# SimpleCharger-LiIon-OpampBased-LM358.net
KiCad netlist of a schematic drawn in EAGLE
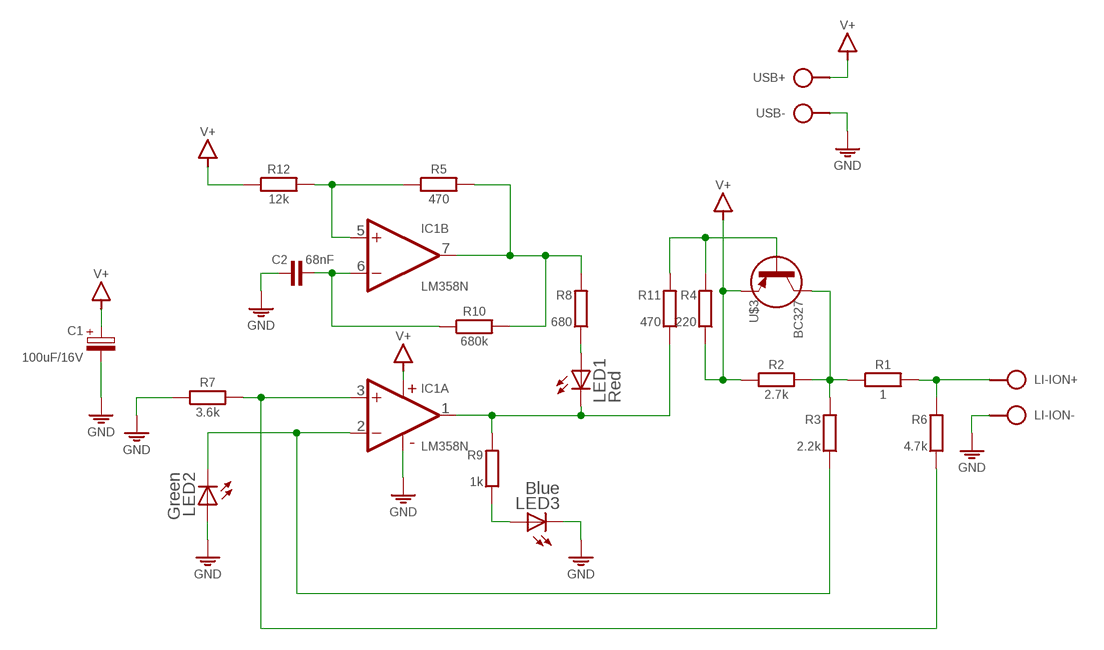
[diagram p0: schematic, sheet 1]

(export (version "E")
  (design (tool "Eeschema 10.0.6"))
  (components
    (comp (ref "C1")
      (value "100uF/16V")
      (footprint "eagle-import:E2,5-5")
      (libsource (lib "eagle-import") (part "CPOLE2.5-5"))
    )
    (comp (ref "C2")
      (value "68nF")
      (footprint "eagle-import:C075-020X044_V")
      (libsource (lib "eagle-import") (part "C-H075-020X044/V"))
    )
    (comp (ref "IC1")
      (value "LM358N")
      (footprint "eagle-import:DIL08")
      (libsource (lib "eagle-import") (part "LM358N"))
    )
    (comp (ref "LED1")
      (value "Red")
      (footprint "eagle-import:LED3MM")
      (libsource (lib "eagle-import") (part "LED3MM"))
    )
    (comp (ref "LED2")
      (value "Green")
      (footprint "eagle-import:LED3MM")
      (libsource (lib "eagle-import") (part "LED3MM"))
    )
    (comp (ref "LED3")
      (value "Blue")
      (footprint "eagle-import:LED3MM")
      (libsource (lib "eagle-import") (part "LED3MM"))
    )
    (comp (ref "LI-ION")
      (value "SPAD+-+-")
      (footprint "eagle-import:SPAD+-")
      (libsource (lib "eagle-import") (part "SPAD+-+-"))
    )
    (comp (ref "R1")
      (value "1")
      (footprint "eagle-import:0204_10")
      (libsource (lib "eagle-import") (part "R-H0204/10"))
    )
    (comp (ref "R2")
      (value "2.7k")
      (footprint "eagle-import:0204_10-V")
      (libsource (lib "eagle-import") (part "R-H0204/10-V"))
    )
    (comp (ref "R3")
      (value "2.2k")
      (footprint "eagle-import:0204_10-V")
      (libsource (lib "eagle-import") (part "R0204/10-V"))
    )
    (comp (ref "R4")
      (value "220")
      (footprint "eagle-import:0204_10-V")
      (libsource (lib "eagle-import") (part "R0204/10-V"))
    )
    (comp (ref "R5")
      (value "470")
      (footprint "eagle-import:0204_7-V")
      (libsource (lib "eagle-import") (part "R-H0204/7-V"))
    )
    (comp (ref "R6")
      (value "4.7k")
      (footprint "eagle-import:0204_10-V")
      (libsource (lib "eagle-import") (part "R0204/10-V"))
    )
    (comp (ref "R7")
      (value "3.6k")
      (footprint "eagle-import:0204_10")
      (libsource (lib "eagle-import") (part "R-H0204/10"))
    )
    (comp (ref "R8")
      (value "680")
      (footprint "eagle-import:0204_10-V")
      (libsource (lib "eagle-import") (part "R0204/10-V"))
    )
    (comp (ref "R9")
      (value "1k")
      (footprint "eagle-import:0204_10")
      (libsource (lib "eagle-import") (part "R0204/10"))
    )
    (comp (ref "R10")
      (value "680k")
      (footprint "eagle-import:0204_10-V")
      (libsource (lib "eagle-import") (part "R-H0204/10-V"))
    )
    (comp (ref "R11")
      (value "470")
      (footprint "eagle-import:0204_10-V")
      (libsource (lib "eagle-import") (part "R0204/10-V"))
    )
    (comp (ref "R12")
      (value "12k")
      (footprint "eagle-import:0204_10-V")
      (libsource (lib "eagle-import") (part "R-H0204/10-V"))
    )
    (comp (ref "U$3")
      (value "BC327")
      (footprint "eagle-import:TO92")
      (libsource (lib "eagle-import") (part "BC327"))
    )
    (comp (ref "USB")
      (value "SPAD+--+")
      (footprint "eagle-import:SPAD-+")
      (libsource (lib "eagle-import") (part "SPAD+--+"))
    )
  )
  (nets
    (net (code "1") (name "GND") (class "Default")
      (node (ref "C1") (pin "-") (pinfunction "-_-") (pintype "passive"))
      (node (ref "C2") (pin "1") (pinfunction "1_1") (pintype "passive"))
      (node (ref "IC1") (pin "4") (pinfunction "V-_4") (pintype "power_in"))
      (node (ref "LED2") (pin "A") (pinfunction "A_A") (pintype "passive"))
      (node (ref "LED3") (pin "K") (pinfunction "C_K") (pintype "passive"))
      (node (ref "LI-ION") (pin "1") (pinfunction "P$1_1") (pintype "passive"))
      (node (ref "R7") (pin "1") (pinfunction "1_1") (pintype "passive"))
      (node (ref "USB") (pin "1") (pinfunction "P$1_1") (pintype "passive"))
    )
    (net (code "2") (name "Net-(IC1A-+IN)") (class "Default")
      (node (ref "IC1") (pin "3") (pinfunction "+IN_3") (pintype "input"))
      (node (ref "R6") (pin "2") (pinfunction "2_2") (pintype "passive"))
      (node (ref "R7") (pin "2") (pinfunction "2_2") (pintype "passive"))
    )
    (net (code "3") (name "Net-(IC1A--IN)") (class "Default")
      (node (ref "IC1") (pin "2") (pinfunction "-IN_2") (pintype "input"))
      (node (ref "LED2") (pin "K") (pinfunction "C_K") (pintype "passive"))
      (node (ref "R3") (pin "2") (pinfunction "2_2") (pintype "passive"))
    )
    (net (code "4") (name "Net-(IC1A-OUT)") (class "Default")
      (node (ref "IC1") (pin "1") (pinfunction "OUT_1") (pintype "output"))
      (node (ref "LED1") (pin "K") (pinfunction "C_K") (pintype "passive"))
      (node (ref "R11") (pin "2") (pinfunction "2_2") (pintype "passive"))
      (node (ref "R9") (pin "2") (pinfunction "1_2") (pintype "passive"))
    )
    (net (code "5") (name "Net-(IC1B-+IN)") (class "Default")
      (node (ref "IC1") (pin "5") (pinfunction "+IN_5") (pintype "input"))
      (node (ref "R12") (pin "2") (pinfunction "2_2") (pintype "passive"))
      (node (ref "R5") (pin "1") (pinfunction "1_1") (pintype "passive"))
    )
    (net (code "6") (name "Net-(IC1B--IN)") (class "Default")
      (node (ref "C2") (pin "2") (pinfunction "2_2") (pintype "passive"))
      (node (ref "IC1") (pin "6") (pinfunction "-IN_6") (pintype "input"))
      (node (ref "R10") (pin "1") (pinfunction "1_1") (pintype "passive"))
    )
    (net (code "7") (name "Net-(IC1B-OUT)") (class "Default")
      (node (ref "IC1") (pin "7") (pinfunction "OUT_7") (pintype "output"))
      (node (ref "R10") (pin "2") (pinfunction "2_2") (pintype "passive"))
      (node (ref "R5") (pin "2") (pinfunction "2_2") (pintype "passive"))
      (node (ref "R8") (pin "1") (pinfunction "1_1") (pintype "passive"))
    )
    (net (code "8") (name "Net-(LED1-PadA)") (class "Default")
      (node (ref "LED1") (pin "A") (pinfunction "A_A") (pintype "passive"))
      (node (ref "R8") (pin "2") (pinfunction "2_2") (pintype "passive"))
    )
    (net (code "9") (name "Net-(LI-IONA-P$1)") (class "Default")
      (node (ref "LI-ION") (pin "2") (pinfunction "P$1_2") (pintype "passive"))
      (node (ref "R1") (pin "2") (pinfunction "2_2") (pintype "passive"))
      (node (ref "R6") (pin "1") (pinfunction "1_1") (pintype "passive"))
    )
    (net (code "10") (name "Net-(R9-2)") (class "Default")
      (node (ref "LED3") (pin "A") (pinfunction "A_A") (pintype "passive"))
      (node (ref "R9") (pin "1") (pinfunction "2_1") (pintype "passive"))
    )
    (net (code "11") (name "Net-(U$3-B)") (class "Default")
      (node (ref "R11") (pin "1") (pinfunction "1_1") (pintype "passive"))
      (node (ref "R4") (pin "1") (pinfunction "1_1") (pintype "passive"))
      (node (ref "U$3") (pin "2") (pinfunction "B_2") (pintype "passive"))
    )
    (net (code "12") (name "Net-(U$3-C)") (class "Default")
      (node (ref "R1") (pin "1") (pinfunction "1_1") (pintype "passive"))
      (node (ref "R2") (pin "2") (pinfunction "2_2") (pintype "passive"))
      (node (ref "R3") (pin "1") (pinfunction "1_1") (pintype "passive"))
      (node (ref "U$3") (pin "1") (pinfunction "C_1") (pintype "passive"))
    )
    (net (code "13") (name "V+") (class "Default")
      (node (ref "C1") (pin "+") (pinfunction "+_+") (pintype "passive"))
      (node (ref "IC1") (pin "8") (pinfunction "V+_8") (pintype "power_in"))
      (node (ref "R12") (pin "1") (pinfunction "1_1") (pintype "passive"))
      (node (ref "R2") (pin "1") (pinfunction "1_1") (pintype "passive"))
      (node (ref "R4") (pin "2") (pinfunction "2_2") (pintype "passive"))
      (node (ref "U$3") (pin "3") (pinfunction "E_3") (pintype "passive"))
      (node (ref "USB") (pin "2") (pinfunction "P$1_2") (pintype "passive"))
    )
  )
)
